# Driver_parra.net
KiCad netlist of a schematic drawn in EAGLE
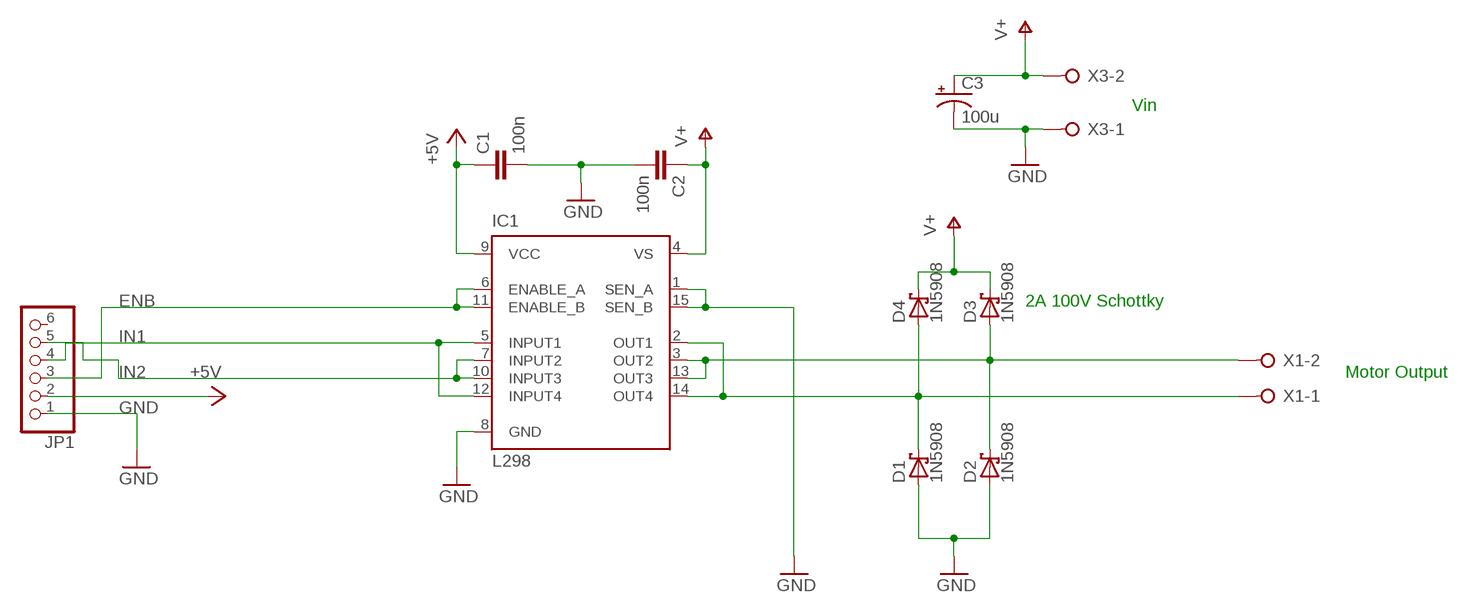
[diagram p0: schematic, sheet 1]

(export (version "E")
  (design (tool "Eeschema 10.0.6"))
  (components
    (comp (ref "C1")
      (value "100n")
      (footprint "eagle-import:C0805K")
      (libsource (lib "eagle-import") (part "C-EUC0805K"))
    )
    (comp (ref "C2")
      (value "100n")
      (footprint "eagle-import:C0805K")
      (libsource (lib "eagle-import") (part "C-EUC0805K"))
    )
    (comp (ref "C3")
      (value "100u")
      (footprint "eagle-import:E7,5-16")
      (libsource (lib "eagle-import") (part "CPOL-USE7.5-16"))
    )
    (comp (ref "D1")
      (value "1N5908")
      (footprint "eagle-import:C4111-15")
      (libsource (lib "eagle-import") (part "1N5908"))
    )
    (comp (ref "D2")
      (value "1N5908")
      (footprint "eagle-import:C4111-15")
      (libsource (lib "eagle-import") (part "1N5908"))
    )
    (comp (ref "D3")
      (value "1N5908")
      (footprint "eagle-import:C4111-15")
      (libsource (lib "eagle-import") (part "1N5908"))
    )
    (comp (ref "D4")
      (value "1N5908")
      (footprint "eagle-import:C4111-15")
      (libsource (lib "eagle-import") (part "1N5908"))
    )
    (comp (ref "IC1")
      (value "L298")
      (footprint "eagle-import:MULTIWATT-15")
      (fields (field (name "MPN") "L298N"))
      (libsource (lib "eagle-import") (part "L298"))
    )
    (comp (ref "JP1")
      (value "PINHD-1X6")
      (footprint "eagle-import:1X06")
      (libsource (lib "eagle-import") (part "PINHD-1X6"))
    )
    (comp (ref "X1")
      (value "W237-02P")
      (footprint "eagle-import:W237-132")
      (libsource (lib "eagle-import") (part "W237-02P"))
    )
    (comp (ref "X3")
      (value "W237-02P")
      (footprint "eagle-import:W237-132")
      (libsource (lib "eagle-import") (part "W237-02P"))
    )
  )
  (nets
    (net (code "1") (name "+5V") (class "Default")
      (node (ref "C1") (pin "1") (pinfunction "1_1") (pintype "passive"))
      (node (ref "IC1") (pin "9") (pinfunction "VCC_9") (pintype "power_in"))
      (node (ref "JP1") (pin "2") (pinfunction "2_2") (pintype "passive"))
    )
    (net (code "2") (name "/ENB") (class "Default")
      (node (ref "IC1") (pin "11") (pinfunction "ENABLE_B_11") (pintype "input"))
      (node (ref "IC1") (pin "6") (pinfunction "ENABLE_A_6") (pintype "input"))
      (node (ref "JP1") (pin "3") (pinfunction "3_3") (pintype "passive"))
    )
    (net (code "3") (name "/IN1") (class "Default")
      (node (ref "IC1") (pin "12") (pinfunction "INPUT4_12") (pintype "input"))
      (node (ref "IC1") (pin "5") (pinfunction "INPUT1_5") (pintype "input"))
      (node (ref "JP1") (pin "4") (pinfunction "4_4") (pintype "passive"))
    )
    (net (code "4") (name "/IN2") (class "Default")
      (node (ref "IC1") (pin "10") (pinfunction "INPUT3_10") (pintype "input"))
      (node (ref "IC1") (pin "7") (pinfunction "INPUT2_7") (pintype "input"))
      (node (ref "JP1") (pin "5") (pinfunction "5_5") (pintype "passive"))
    )
    (net (code "5") (name "GND") (class "Default")
      (node (ref "C1") (pin "2") (pinfunction "2_2") (pintype "passive"))
      (node (ref "C2") (pin "2") (pinfunction "2_2") (pintype "passive"))
      (node (ref "C3") (pin "-") (pinfunction "-_-") (pintype "passive"))
      (node (ref "D1") (pin "A") (pinfunction "A_A") (pintype "passive"))
      (node (ref "D2") (pin "A") (pinfunction "A_A") (pintype "passive"))
      (node (ref "IC1") (pin "1") (pinfunction "SEN_A_1") (pintype "input"))
      (node (ref "IC1") (pin "15") (pinfunction "SEN_B_15") (pintype "input"))
      (node (ref "IC1") (pin "8") (pinfunction "GND_8") (pintype "power_in"))
      (node (ref "JP1") (pin "1") (pinfunction "1_1") (pintype "passive"))
      (node (ref "X3") (pin "1") (pinfunction "KL_1") (pintype "passive"))
    )
    (net (code "6") (name "Net-(IC1-OUT1)") (class "Default")
      (node (ref "D1") (pin "C") (pinfunction "C_C") (pintype "passive"))
      (node (ref "D4") (pin "A") (pinfunction "A_A") (pintype "passive"))
      (node (ref "IC1") (pin "14") (pinfunction "OUT4_14") (pintype "output"))
      (node (ref "IC1") (pin "2") (pinfunction "OUT1_2") (pintype "output"))
      (node (ref "X1") (pin "1") (pinfunction "KL_1") (pintype "passive"))
    )
    (net (code "7") (name "Net-(IC1-OUT2)") (class "Default")
      (node (ref "D2") (pin "C") (pinfunction "C_C") (pintype "passive"))
      (node (ref "D3") (pin "A") (pinfunction "A_A") (pintype "passive"))
      (node (ref "IC1") (pin "13") (pinfunction "OUT3_13") (pintype "output"))
      (node (ref "IC1") (pin "3") (pinfunction "OUT2_3") (pintype "output"))
      (node (ref "X1") (pin "2") (pinfunction "KL_2") (pintype "passive"))
    )
    (net (code "8") (name "V+") (class "Default")
      (node (ref "C2") (pin "1") (pinfunction "1_1") (pintype "passive"))
      (node (ref "C3") (pin "+") (pinfunction "+_+") (pintype "passive"))
      (node (ref "D3") (pin "C") (pinfunction "C_C") (pintype "passive"))
      (node (ref "D4") (pin "C") (pinfunction "C_C") (pintype "passive"))
      (node (ref "IC1") (pin "4") (pinfunction "VS_4") (pintype "power_in"))
      (node (ref "X3") (pin "2") (pinfunction "KL_2") (pintype "passive"))
    )
    (net (code "9") (name "unconnected-(JP1-Pad6)") (class "Default")
      (node (ref "JP1") (pin "6") (pinfunction "6_6") (pintype "passive"))
    )
  )
)
